# ESC_4in1.net
KiCad netlist of a schematic drawn in Altium Designer
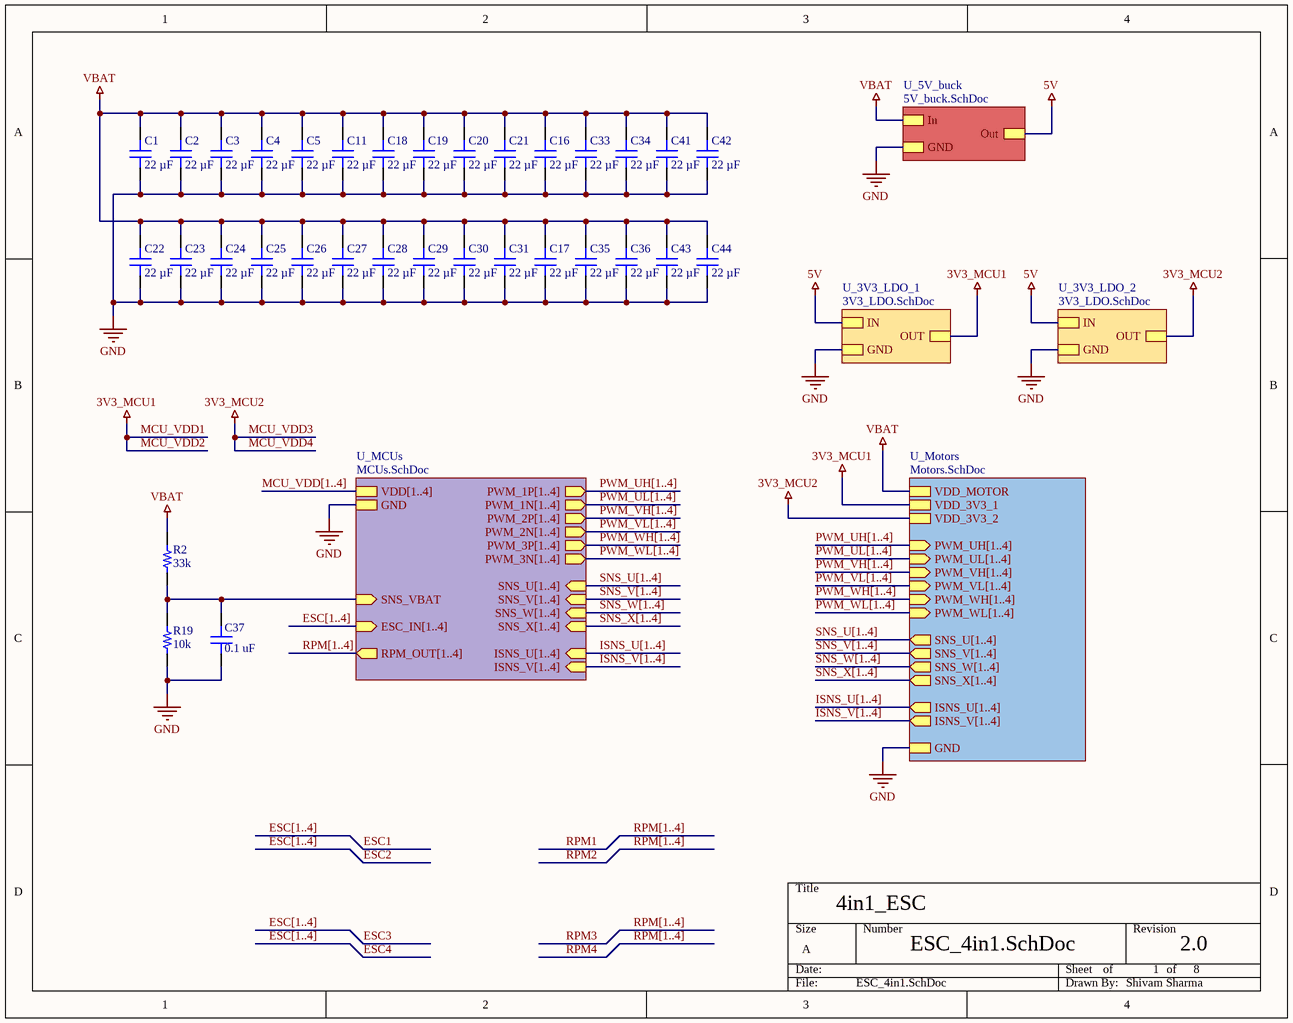
[diagram p0: ESC_4in1.SchDoc]

(export (version "E")
  (design (tool "Eeschema 10.0.6"))
  (components
    (comp (ref "C1")
      (value "22 µF")
      (footprint "CAP 0805_2012")
      (description "CAP CER 22UF 25V X5R 0805")
      (fields (field (name "PART NUMBER") "CC0805MKX5R8BB226") (field (name "MANUFACTURER") "Yageo"))
      (libsource (lib "Celestial Altium Library - altium_library") (part "Capacitor"))
    )
    (comp (ref "C2")
      (value "22 µF")
      (footprint "CAP 0805_2012")
      (description "CAP CER 22UF 25V X5R 0805")
      (fields (field (name "PART NUMBER") "CC0805MKX5R8BB226") (field (name "MANUFACTURER") "Yageo"))
      (libsource (lib "Celestial Altium Library - altium_library") (part "Capacitor"))
    )
    (comp (ref "C3")
      (value "22 µF")
      (footprint "CAP 0805_2012")
      (description "CAP CER 22UF 25V X5R 0805")
      (fields (field (name "PART NUMBER") "CC0805MKX5R8BB226") (field (name "MANUFACTURER") "Yageo"))
      (libsource (lib "Celestial Altium Library - altium_library") (part "Capacitor"))
    )
    (comp (ref "C4")
      (value "22 µF")
      (footprint "CAP 0805_2012")
      (description "CAP CER 22UF 25V X5R 0805")
      (fields (field (name "PART NUMBER") "CC0805MKX5R8BB226") (field (name "MANUFACTURER") "Yageo"))
      (libsource (lib "Celestial Altium Library - altium_library") (part "Capacitor"))
    )
    (comp (ref "C5")
      (value "22 µF")
      (footprint "CAP 0805_2012")
      (description "CAP CER 22UF 25V X5R 0805")
      (fields (field (name "PART NUMBER") "CC0805MKX5R8BB226") (field (name "MANUFACTURER") "Yageo"))
      (libsource (lib "Celestial Altium Library - altium_library") (part "Capacitor"))
    )
    (comp (ref "C11")
      (value "22 µF")
      (footprint "CAP 0805_2012")
      (description "CAP CER 22UF 25V X5R 0805")
      (fields (field (name "PART NUMBER") "CC0805MKX5R8BB226") (field (name "MANUFACTURER") "Yageo"))
      (libsource (lib "Celestial Altium Library - altium_library") (part "Capacitor"))
    )
    (comp (ref "C16")
      (value "22 µF")
      (footprint "CAP 0805_2012")
      (description "CAP CER 22UF 25V X5R 0805")
      (fields (field (name "PART NUMBER") "CC0805MKX5R8BB226") (field (name "MANUFACTURER") "Yageo"))
      (libsource (lib "Celestial Altium Library - altium_library") (part "Capacitor"))
    )
    (comp (ref "C17")
      (value "22 µF")
      (footprint "CAP 0805_2012")
      (description "CAP CER 22UF 25V X5R 0805")
      (fields (field (name "PART NUMBER") "CC0805MKX5R8BB226") (field (name "MANUFACTURER") "Yageo"))
      (libsource (lib "Celestial Altium Library - altium_library") (part "Capacitor"))
    )
    (comp (ref "C18")
      (value "22 µF")
      (footprint "CAP 0805_2012")
      (description "CAP CER 22UF 25V X5R 0805")
      (fields (field (name "PART NUMBER") "CC0805MKX5R8BB226") (field (name "MANUFACTURER") "Yageo"))
      (libsource (lib "Celestial Altium Library - altium_library") (part "Capacitor"))
    )
    (comp (ref "C19")
      (value "22 µF")
      (footprint "CAP 0805_2012")
      (description "CAP CER 22UF 25V X5R 0805")
      (fields (field (name "PART NUMBER") "CC0805MKX5R8BB226") (field (name "MANUFACTURER") "Yageo"))
      (libsource (lib "Celestial Altium Library - altium_library") (part "Capacitor"))
    )
    (comp (ref "C20")
      (value "22 µF")
      (footprint "CAP 0805_2012")
      (description "CAP CER 22UF 25V X5R 0805")
      (fields (field (name "PART NUMBER") "CC0805MKX5R8BB226") (field (name "MANUFACTURER") "Yageo"))
      (libsource (lib "Celestial Altium Library - altium_library") (part "Capacitor"))
    )
    (comp (ref "C21")
      (value "22 µF")
      (footprint "CAP 0805_2012")
      (description "CAP CER 22UF 25V X5R 0805")
      (fields (field (name "PART NUMBER") "CC0805MKX5R8BB226") (field (name "MANUFACTURER") "Yageo"))
      (libsource (lib "Celestial Altium Library - altium_library") (part "Capacitor"))
    )
    (comp (ref "C22")
      (value "22 µF")
      (footprint "CAP 0805_2012")
      (description "CAP CER 22UF 25V X5R 0805")
      (fields (field (name "PART NUMBER") "CC0805MKX5R8BB226") (field (name "MANUFACTURER") "Yageo"))
      (libsource (lib "Celestial Altium Library - altium_library") (part "Capacitor"))
    )
    (comp (ref "C23")
      (value "22 µF")
      (footprint "CAP 0805_2012")
      (description "CAP CER 22UF 25V X5R 0805")
      (fields (field (name "PART NUMBER") "CC0805MKX5R8BB226") (field (name "MANUFACTURER") "Yageo"))
      (libsource (lib "Celestial Altium Library - altium_library") (part "Capacitor"))
    )
    (comp (ref "C24")
      (value "22 µF")
      (footprint "CAP 0805_2012")
      (description "CAP CER 22UF 25V X5R 0805")
      (fields (field (name "PART NUMBER") "CC0805MKX5R8BB226") (field (name "MANUFACTURER") "Yageo"))
      (libsource (lib "Celestial Altium Library - altium_library") (part "Capacitor"))
    )
    (comp (ref "C25")
      (value "22 µF")
      (footprint "CAP 0805_2012")
      (description "CAP CER 22UF 25V X5R 0805")
      (fields (field (name "PART NUMBER") "CC0805MKX5R8BB226") (field (name "MANUFACTURER") "Yageo"))
      (libsource (lib "Celestial Altium Library - altium_library") (part "Capacitor"))
    )
    (comp (ref "C26")
      (value "22 µF")
      (footprint "CAP 0805_2012")
      (description "CAP CER 22UF 25V X5R 0805")
      (fields (field (name "PART NUMBER") "CC0805MKX5R8BB226") (field (name "MANUFACTURER") "Yageo"))
      (libsource (lib "Celestial Altium Library - altium_library") (part "Capacitor"))
    )
    (comp (ref "C27")
      (value "22 µF")
      (footprint "CAP 0805_2012")
      (description "CAP CER 22UF 25V X5R 0805")
      (fields (field (name "PART NUMBER") "CC0805MKX5R8BB226") (field (name "MANUFACTURER") "Yageo"))
      (libsource (lib "Celestial Altium Library - altium_library") (part "Capacitor"))
    )
    (comp (ref "C28")
      (value "22 µF")
      (footprint "CAP 0805_2012")
      (description "CAP CER 22UF 25V X5R 0805")
      (fields (field (name "PART NUMBER") "CC0805MKX5R8BB226") (field (name "MANUFACTURER") "Yageo"))
      (libsource (lib "Celestial Altium Library - altium_library") (part "Capacitor"))
    )
    (comp (ref "C29")
      (value "22 µF")
      (footprint "CAP 0805_2012")
      (description "CAP CER 22UF 25V X5R 0805")
      (fields (field (name "PART NUMBER") "CC0805MKX5R8BB226") (field (name "MANUFACTURER") "Yageo"))
      (libsource (lib "Celestial Altium Library - altium_library") (part "Capacitor"))
    )
    (comp (ref "C30")
      (value "22 µF")
      (footprint "CAP 0805_2012")
      (description "CAP CER 22UF 25V X5R 0805")
      (fields (field (name "PART NUMBER") "CC0805MKX5R8BB226") (field (name "MANUFACTURER") "Yageo"))
      (libsource (lib "Celestial Altium Library - altium_library") (part "Capacitor"))
    )
    (comp (ref "C31")
      (value "22 µF")
      (footprint "CAP 0805_2012")
      (description "CAP CER 22UF 25V X5R 0805")
      (fields (field (name "PART NUMBER") "CC0805MKX5R8BB226") (field (name "MANUFACTURER") "Yageo"))
      (libsource (lib "Celestial Altium Library - altium_library") (part "Capacitor"))
    )
    (comp (ref "C33")
      (value "22 µF")
      (footprint "CAP 0805_2012")
      (description "CAP CER 22UF 25V X5R 0805")
      (fields (field (name "PART NUMBER") "CC0805MKX5R8BB226") (field (name "MANUFACTURER") "Yageo"))
      (libsource (lib "Celestial Altium Library - altium_library") (part "Capacitor"))
    )
    (comp (ref "C34")
      (value "22 µF")
      (footprint "CAP 0805_2012")
      (description "CAP CER 22UF 25V X5R 0805")
      (fields (field (name "PART NUMBER") "CC0805MKX5R8BB226") (field (name "MANUFACTURER") "Yageo"))
      (libsource (lib "Celestial Altium Library - altium_library") (part "Capacitor"))
    )
    (comp (ref "C35")
      (value "22 µF")
      (footprint "CAP 0805_2012")
      (description "CAP CER 22UF 25V X5R 0805")
      (fields (field (name "PART NUMBER") "CC0805MKX5R8BB226") (field (name "MANUFACTURER") "Yageo"))
      (libsource (lib "Celestial Altium Library - altium_library") (part "Capacitor"))
    )
    (comp (ref "C36")
      (value "22 µF")
      (footprint "CAP 0805_2012")
      (description "CAP CER 22UF 25V X5R 0805")
      (fields (field (name "PART NUMBER") "CC0805MKX5R8BB226") (field (name "MANUFACTURER") "Yageo"))
      (libsource (lib "Celestial Altium Library - altium_library") (part "Capacitor"))
    )
    (comp (ref "C37")
      (value "0.1 uF")
      (footprint "CAP 0201_0603")
      (description "CAP CER 0.1UF 35V X5R 0201")
      (fields
        (field (name "PART NUMBER") "GRT033R6YA104KE01D")
        (field (name "MANUFACTURER") "Murata Electronics")
      )
      (libsource (lib "Celestial Altium Library - altium_library") (part "Capacitor"))
    )
    (comp (ref "C41")
      (value "22 µF")
      (footprint "CAP 0805_2012")
      (description "CAP CER 22UF 25V X5R 0805")
      (fields (field (name "PART NUMBER") "CC0805MKX5R8BB226") (field (name "MANUFACTURER") "Yageo"))
      (libsource (lib "Celestial Altium Library - altium_library") (part "Capacitor"))
    )
    (comp (ref "C42")
      (value "22 µF")
      (footprint "CAP 0805_2012")
      (description "CAP CER 22UF 25V X5R 0805")
      (fields (field (name "PART NUMBER") "CC0805MKX5R8BB226") (field (name "MANUFACTURER") "Yageo"))
      (libsource (lib "Celestial Altium Library - altium_library") (part "Capacitor"))
    )
    (comp (ref "C43")
      (value "22 µF")
      (footprint "CAP 0805_2012")
      (description "CAP CER 22UF 25V X5R 0805")
      (fields (field (name "PART NUMBER") "CC0805MKX5R8BB226") (field (name "MANUFACTURER") "Yageo"))
      (libsource (lib "Celestial Altium Library - altium_library") (part "Capacitor"))
    )
    (comp (ref "C44")
      (value "22 µF")
      (footprint "CAP 0805_2012")
      (description "CAP CER 22UF 25V X5R 0805")
      (fields (field (name "PART NUMBER") "CC0805MKX5R8BB226") (field (name "MANUFACTURER") "Yageo"))
      (libsource (lib "Celestial Altium Library - altium_library") (part "Capacitor"))
    )
    (comp (ref "R2")
      (value "33k")
      (footprint "RES 0201_0603")
      (description "RES SMD 10K OHM 1% 1/20W 0201")
      (fields (field (name "PART NUMBER") "CRCW020110K0FKED") (field (name "MANUFACTURER") "Vishay Dale"))
      (libsource (lib "Celestial Altium Library - altium_library") (part "Resistor"))
    )
    (comp (ref "R19")
      (value "10k")
      (footprint "RES 0201_0603")
      (description "RES SMD 10K OHM 1% 1/20W 0201")
      (fields (field (name "PART NUMBER") "CRCW020110K0FKED") (field (name "MANUFACTURER") "Vishay Dale"))
      (libsource (lib "Celestial Altium Library - altium_library") (part "Resistor"))
    )
  )
  (nets
    (net (code "69") (name "/SNS_VBAT") (class "Default")
      (node (ref "C37") (pin "2") (pinfunction "2_2") (pintype "passive"))
      (node (ref "R19") (pin "2") (pinfunction "2_2") (pintype "passive"))
      (node (ref "R2") (pin "1") (pinfunction "1_1") (pintype "passive"))
    )
    (net (code "76") (name "GND") (class "Default")
      (node (ref "C1") (pin "1") (pinfunction "1_1") (pintype "passive"))
      (node (ref "C11") (pin "1") (pinfunction "1_1") (pintype "passive"))
      (node (ref "C16") (pin "1") (pinfunction "1_1") (pintype "passive"))
      (node (ref "C17") (pin "1") (pinfunction "1_1") (pintype "passive"))
      (node (ref "C18") (pin "1") (pinfunction "1_1") (pintype "passive"))
      (node (ref "C19") (pin "1") (pinfunction "1_1") (pintype "passive"))
      (node (ref "C2") (pin "1") (pinfunction "1_1") (pintype "passive"))
      (node (ref "C20") (pin "1") (pinfunction "1_1") (pintype "passive"))
      (node (ref "C21") (pin "1") (pinfunction "1_1") (pintype "passive"))
      (node (ref "C22") (pin "1") (pinfunction "1_1") (pintype "passive"))
      (node (ref "C23") (pin "1") (pinfunction "1_1") (pintype "passive"))
      (node (ref "C24") (pin "1") (pinfunction "1_1") (pintype "passive"))
      (node (ref "C25") (pin "1") (pinfunction "1_1") (pintype "passive"))
      (node (ref "C26") (pin "1") (pinfunction "1_1") (pintype "passive"))
      (node (ref "C27") (pin "1") (pinfunction "1_1") (pintype "passive"))
      (node (ref "C28") (pin "1") (pinfunction "1_1") (pintype "passive"))
      (node (ref "C29") (pin "1") (pinfunction "1_1") (pintype "passive"))
      (node (ref "C3") (pin "1") (pinfunction "1_1") (pintype "passive"))
      (node (ref "C30") (pin "1") (pinfunction "1_1") (pintype "passive"))
      (node (ref "C31") (pin "1") (pinfunction "1_1") (pintype "passive"))
      (node (ref "C33") (pin "1") (pinfunction "1_1") (pintype "passive"))
      (node (ref "C34") (pin "1") (pinfunction "1_1") (pintype "passive"))
      (node (ref "C35") (pin "1") (pinfunction "1_1") (pintype "passive"))
      (node (ref "C36") (pin "1") (pinfunction "1_1") (pintype "passive"))
      (node (ref "C37") (pin "1") (pinfunction "1_1") (pintype "passive"))
      (node (ref "C4") (pin "1") (pinfunction "1_1") (pintype "passive"))
      (node (ref "C41") (pin "1") (pinfunction "1_1") (pintype "passive"))
      (node (ref "C42") (pin "1") (pinfunction "1_1") (pintype "passive"))
      (node (ref "C43") (pin "1") (pinfunction "1_1") (pintype "passive"))
      (node (ref "C44") (pin "1") (pinfunction "1_1") (pintype "passive"))
      (node (ref "C5") (pin "1") (pinfunction "1_1") (pintype "passive"))
      (node (ref "R19") (pin "1") (pinfunction "1_1") (pintype "passive"))
    )
    (net (code "77") (name "VBAT") (class "Default")
      (node (ref "C1") (pin "2") (pinfunction "2_2") (pintype "passive"))
      (node (ref "C11") (pin "2") (pinfunction "2_2") (pintype "passive"))
      (node (ref "C16") (pin "2") (pinfunction "2_2") (pintype "passive"))
      (node (ref "C17") (pin "2") (pinfunction "2_2") (pintype "passive"))
      (node (ref "C18") (pin "2") (pinfunction "2_2") (pintype "passive"))
      (node (ref "C19") (pin "2") (pinfunction "2_2") (pintype "passive"))
      (node (ref "C2") (pin "2") (pinfunction "2_2") (pintype "passive"))
      (node (ref "C20") (pin "2") (pinfunction "2_2") (pintype "passive"))
      (node (ref "C21") (pin "2") (pinfunction "2_2") (pintype "passive"))
      (node (ref "C22") (pin "2") (pinfunction "2_2") (pintype "passive"))
      (node (ref "C23") (pin "2") (pinfunction "2_2") (pintype "passive"))
      (node (ref "C24") (pin "2") (pinfunction "2_2") (pintype "passive"))
      (node (ref "C25") (pin "2") (pinfunction "2_2") (pintype "passive"))
      (node (ref "C26") (pin "2") (pinfunction "2_2") (pintype "passive"))
      (node (ref "C27") (pin "2") (pinfunction "2_2") (pintype "passive"))
      (node (ref "C28") (pin "2") (pinfunction "2_2") (pintype "passive"))
      (node (ref "C29") (pin "2") (pinfunction "2_2") (pintype "passive"))
      (node (ref "C3") (pin "2") (pinfunction "2_2") (pintype "passive"))
      (node (ref "C30") (pin "2") (pinfunction "2_2") (pintype "passive"))
      (node (ref "C31") (pin "2") (pinfunction "2_2") (pintype "passive"))
      (node (ref "C33") (pin "2") (pinfunction "2_2") (pintype "passive"))
      (node (ref "C34") (pin "2") (pinfunction "2_2") (pintype "passive"))
      (node (ref "C35") (pin "2") (pinfunction "2_2") (pintype "passive"))
      (node (ref "C36") (pin "2") (pinfunction "2_2") (pintype "passive"))
      (node (ref "C4") (pin "2") (pinfunction "2_2") (pintype "passive"))
      (node (ref "C41") (pin "2") (pinfunction "2_2") (pintype "passive"))
      (node (ref "C42") (pin "2") (pinfunction "2_2") (pintype "passive"))
      (node (ref "C43") (pin "2") (pinfunction "2_2") (pintype "passive"))
      (node (ref "C44") (pin "2") (pinfunction "2_2") (pintype "passive"))
      (node (ref "C5") (pin "2") (pinfunction "2_2") (pintype "passive"))
      (node (ref "R2") (pin "2") (pinfunction "2_2") (pintype "passive"))
    )
  )
)
